# Power.net
KiCad netlist of a schematic drawn in Altium Designer
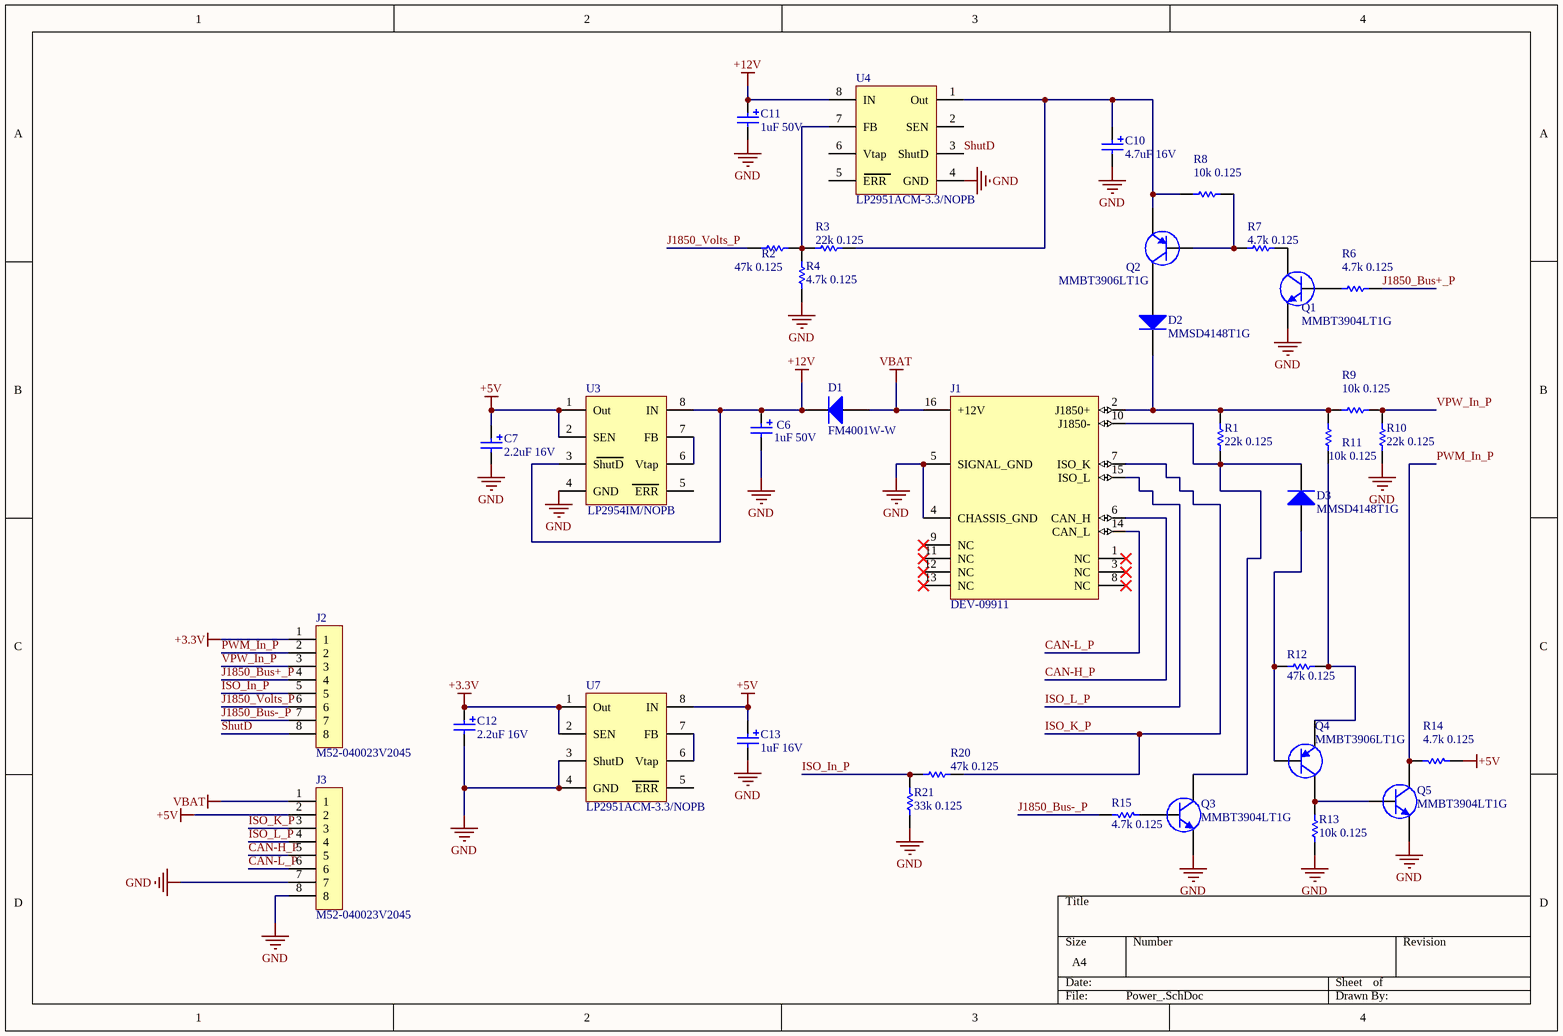
[diagram p0: Power_.SchDoc]

(export (version "E")
  (design (tool "Eeschema 10.0.6"))
  (components
    (comp (ref "C6")
      (value "1uF 50V")
      (footprint "C1005")
      (description "Surface-Mount Electrolitic Tantalum Capacitor, 1uF, 20% Tolerance, 1005 Size, 50V")
      (fields (field (name "PUBLISHER") "Altium Limited"))
      (libsource (lib "OBDII-components") (part "298D105X0050P2T"))
    )
    (comp (ref "C7")
      (value "2.2uF 16V")
      (footprint "C0603")
      (description "Surface-Mount Electrolitic Tantalum Capacitor, 2.2uF, 10% Tolerance, 0603 Size, 16V")
      (fields (field (name "PUBLISHER") "Altium Limited"))
      (libsource (lib "OBDII-components") (part "298D225X0016M2T"))
    )
    (comp (ref "C10")
      (value "4.7uF 16V")
      (footprint "C1005")
      (description "Surface-Mount Electrolitic Tantalum Capacitor, 4.7uF, 20% Tolerance, 1005 Size, 16V")
      (fields (field (name "PUBLISHER") "Altium Limited"))
      (libsource (lib "OBDII-components") (part "298D475X0016P2T"))
    )
    (comp (ref "C11")
      (value "1uF 50V")
      (footprint "C1005")
      (description "Surface-Mount Electrolitic Tantalum Capacitor, 1uF, 20% Tolerance, 1005 Size, 50V")
      (fields (field (name "PUBLISHER") "Altium Limited"))
      (libsource (lib "OBDII-components") (part "298D105X0050P2T"))
    )
    (comp (ref "C12")
      (value "2.2uF 16V")
      (footprint "C0603")
      (description "Surface-Mount Electrolitic Tantalum Capacitor, 2.2uF, 10% Tolerance, 0603 Size, 16V")
      (fields (field (name "PUBLISHER") "Altium Limited"))
      (libsource (lib "OBDII-components") (part "298D225X0016M2T"))
    )
    (comp (ref "C13")
      (value "1uF 16V")
      (footprint "C0603")
      (description "Surface-Mount Electrolitic Tantalum Capacitor, 1uF, 10% Tolerance, 0603 Size, 16V")
      (fields (field (name "PUBLISHER") "Altium Limited"))
      (libsource (lib "OBDII-components") (part "298D105X9016M2T"))
    )
    (comp (ref "D1")
      (value "FM4001W-W")
      (footprint "SMA,2.8mm")
      (description "1 Amp 50V  Rectifier")
      (libsource (lib "OBDII-components") (part "FM4001W-W"))
    )
    (comp (ref "D2")
      (value "MMSD4148T1G")
      (footprint "SOD123")
      (description "High Conductance Fast Diode")
      (fields
        (field (name "MANUFACTURER") "OnSemi")
        (field (name "PUBLISHER") "Vanteon")
        (field (name "APPROVED") "M. Jablonski")
      )
      (libsource (lib "OBDII-components") (part "MMSD4148T1G"))
    )
    (comp (ref "D3")
      (value "MMSD4148T1G")
      (footprint "SOD123")
      (description "High Conductance Fast Diode")
      (fields
        (field (name "MANUFACTURER") "OnSemi")
        (field (name "PUBLISHER") "Vanteon")
        (field (name "APPROVED") "M. Jablonski")
      )
      (libsource (lib "OBDII-components") (part "MMSD4148T1G"))
    )
    (comp (ref "J1")
      (value "DEV-09911")
      (footprint "DEV-09911 - II")
      (description "OBD-II Connector")
      (fields (field (name "MANUFACTURER") "SparkFun Electronics"))
      (libsource (lib "OBDII-components") (part "OBDII_DEV-09911"))
    )
    (comp (ref "J2")
      (value "M52-040023V2045")
      (footprint "M52-040023V2045")
      (description "CONN HEADER .050\" 20POS PCB GOLD")
      (fields (field (name "MANUFACTURER") "Harwin"))
      (libsource (lib "OBDII-components") (part "M52-040023V2045"))
    )
    (comp (ref "J3")
      (value "M52-040023V2045")
      (footprint "M52-040023V2045")
      (description "CONN HEADER .050\" 20POS PCB GOLD")
      (fields (field (name "MANUFACTURER") "Harwin"))
      (libsource (lib "OBDII-components") (part "M52-040023V2045"))
    )
    (comp (ref "Q1")
      (value "MMBT3904LT1G")
      (footprint "SOT23")
      (description "NPN 3904 General Purpose Amplifier")
      (fields
        (field (name "MANUFACTURER") "ON Semiconductor")
        (field (name "PUBLISHER") "Vanteon")
        (field (name "APPROVED") "Yes by Implemenation")
      )
      (libsource (lib "OBDII-components") (part "MMBT3904LT1G"))
    )
    (comp (ref "Q2")
      (value "MMBT3906LT1G")
      (footprint "SOT23")
      (description "PNP 3906 General Purpose Amplifier")
      (fields
        (field (name "MANUFACTURER") "ON Semiconductor")
        (field (name "PUBLISHER") "Vanteon")
        (field (name "APPROVED") "Yes by Implemenation")
      )
      (libsource (lib "OBDII-components") (part "MMBT3906LT1G"))
    )
    (comp (ref "Q3")
      (value "MMBT3904LT1G")
      (footprint "SOT23")
      (description "NPN 3904 General Purpose Amplifier")
      (fields
        (field (name "MANUFACTURER") "ON Semiconductor")
        (field (name "PUBLISHER") "Vanteon")
        (field (name "APPROVED") "Yes by Implemenation")
      )
      (libsource (lib "OBDII-components") (part "MMBT3904LT1G"))
    )
    (comp (ref "Q4")
      (value "MMBT3906LT1G")
      (footprint "SOT23")
      (description "PNP 3906 General Purpose Amplifier")
      (fields
        (field (name "MANUFACTURER") "ON Semiconductor")
        (field (name "PUBLISHER") "Vanteon")
        (field (name "APPROVED") "Yes by Implemenation")
      )
      (libsource (lib "OBDII-components") (part "MMBT3906LT1G"))
    )
    (comp (ref "Q5")
      (value "MMBT3904LT1G")
      (footprint "SOT23")
      (description "NPN 3904 General Purpose Amplifier")
      (fields
        (field (name "MANUFACTURER") "ON Semiconductor")
        (field (name "PUBLISHER") "Vanteon")
        (field (name "APPROVED") "Yes by Implemenation")
      )
      (libsource (lib "OBDII-components") (part "MMBT3904LT1G"))
    )
    (comp (ref "R1")
      (value "22k 0.125")
      (footprint "ERA-0805")
      (description "Rectangular Thick Film Chip Resistor, 22 kOhm, 0.1% Tolerance, 0805 Size, 0.125 W")
      (libsource (lib "OBDII-components") (part "ERA-6AEB223V"))
    )
    (comp (ref "R2")
      (value "47k 0.125")
      (footprint "ERA-0805")
      (description "Rectangular Thick Film Chip Resistor, 47 kOhm, 0.1% Tolerance, 0805 Size, 0.125 W")
      (libsource (lib "OBDII-components") (part "ERA-6AEB473V"))
    )
    (comp (ref "R3")
      (value "22k 0.125")
      (footprint "ERA-0805")
      (description "Rectangular Thick Film Chip Resistor, 22 kOhm, 0.1% Tolerance, 0805 Size, 0.125 W")
      (libsource (lib "OBDII-components") (part "ERA-6AEB223V"))
    )
    (comp (ref "R4")
      (value "4.7k 0.125")
      (footprint "ERA-0805")
      (description "Rectangular Thick Film Chip Resistor, 4.7 kOhm, 0.1% Tolerance, 0805 Size, 0.125 W")
      (libsource (lib "OBDII-components") (part "ERA-6AEB472V"))
    )
    (comp (ref "R6")
      (value "4.7k 0.125")
      (footprint "ERA-0805")
      (description "Rectangular Thick Film Chip Resistor, 4.7 kOhm, 0.1% Tolerance, 0805 Size, 0.125 W")
      (libsource (lib "OBDII-components") (part "ERA-6AEB472V"))
    )
    (comp (ref "R7")
      (value "4.7k 0.125")
      (footprint "ERA-0805")
      (description "Rectangular Thick Film Chip Resistor, 4.7 kOhm, 0.1% Tolerance, 0805 Size, 0.125 W")
      (libsource (lib "OBDII-components") (part "ERA-6AEB472V"))
    )
    (comp (ref "R8")
      (value "10k 0.125")
      (footprint "ERA-0805")
      (description "Rectangular Thick Film Chip Resistor, 10 kOhm, 0.1% Tolerance, 0805 Size, 0.125 W")
      (libsource (lib "OBDII-components") (part "ERA-6AEB103V"))
    )
    (comp (ref "R9")
      (value "10k 0.125")
      (footprint "ERA-0805")
      (description "Rectangular Thick Film Chip Resistor, 10 kOhm, 0.1% Tolerance, 0805 Size, 0.125 W")
      (libsource (lib "OBDII-components") (part "ERA-6AEB103V"))
    )
    (comp (ref "R10")
      (value "22k 0.125")
      (footprint "ERA-0805")
      (description "Rectangular Thick Film Chip Resistor, 22 kOhm, 0.1% Tolerance, 0805 Size, 0.125 W")
      (libsource (lib "OBDII-components") (part "ERA-6AEB223V"))
    )
    (comp (ref "R11")
      (value "10k 0.125")
      (footprint "ERA-0805")
      (description "Rectangular Thick Film Chip Resistor, 10 kOhm, 0.1% Tolerance, 0805 Size, 0.125 W")
      (libsource (lib "OBDII-components") (part "ERA-6AEB103V"))
    )
    (comp (ref "R12")
      (value "47k 0.125")
      (footprint "ERA-0805")
      (description "Rectangular Thick Film Chip Resistor, 47 kOhm, 0.1% Tolerance, 0805 Size, 0.125 W")
      (libsource (lib "OBDII-components") (part "ERA-6AEB473V"))
    )
    (comp (ref "R13")
      (value "10k 0.125")
      (footprint "ERA-0805")
      (description "Rectangular Thick Film Chip Resistor, 10 kOhm, 0.1% Tolerance, 0805 Size, 0.125 W")
      (libsource (lib "OBDII-components") (part "ERA-6AEB103V"))
    )
    (comp (ref "R14")
      (value "4.7k 0.125")
      (footprint "ERA-0805")
      (description "Rectangular Thick Film Chip Resistor, 4.7 kOhm, 0.1% Tolerance, 0805 Size, 0.125 W")
      (libsource (lib "OBDII-components") (part "ERA-6AEB472V"))
    )
    (comp (ref "R15")
      (value "4.7k 0.125")
      (footprint "ERA-0805")
      (description "Rectangular Thick Film Chip Resistor, 4.7 kOhm, 0.1% Tolerance, 0805 Size, 0.125 W")
      (libsource (lib "OBDII-components") (part "ERA-6AEB472V"))
    )
    (comp (ref "R20")
      (value "47k 0.125")
      (footprint "ERA-0805")
      (description "Rectangular Thick Film Chip Resistor, 47 kOhm, 0.1% Tolerance, 0805 Size, 0.125 W")
      (libsource (lib "OBDII-components") (part "ERA-6AEB473V"))
    )
    (comp (ref "R21")
      (value "33k 0.125")
      (footprint "ERA-0805")
      (description "Rectangular Thick Film Chip Resistor, 33 kOhm, 0.1% Tolerance, 0805 Size, 0.125 W")
      (libsource (lib "OBDII-components") (part "ERA-6AEB333V"))
    )
    (comp (ref "U3")
      (value "LP2954IM/NOPB")
      (footprint "SOIC8N")
      (description "LDO Voltage Regulators  1.2V-29V 0.25A SOIC8")
      (fields
        (field (name "MANUFACTURER") "Texas Instruments")
        (field (name "APPROVED") "Yes by Implementation")
      )
      (libsource (lib "OBDII-components") (part "LP2954IM/NOPB"))
    )
    (comp (ref "U4")
      (value "LP2951ACM-3.3/NOPB")
      (footprint "SOIC8N")
      (description "LDO Voltage Regulators  1.2V-37V 0.1A SOIC8")
      (fields
        (field (name "MANUFACTURER") "Texas Instruments")
        (field (name "APPROVED") "Yes by Implementation")
      )
      (libsource (lib "") (part "LP2951ACM-3.3/NOPB_1"))
    )
    (comp (ref "U7")
      (value "LP2951ACM-3.3/NOPB")
      (footprint "SOIC8N")
      (description "LDO Voltage Regulators  1.2V-37V 0.1A SOIC8")
      (fields
        (field (name "MANUFACTURER") "Texas Instruments")
        (field (name "APPROVED") "Yes by Implementation")
      )
      (libsource (lib "OBDII-components") (part "LP2951ACM-3.3/NOPB"))
    )
  )
  (nets
    (net (code "1") (name "+3.3V") (class "Default")
      (node (ref "C12") (pin "1") (pinfunction "1_1") (pintype "passive"))
      (node (ref "J2") (pin "1") (pinfunction "1_1") (pintype "passive"))
      (node (ref "U7") (pin "1") (pinfunction "Out_1") (pintype "power_in"))
      (node (ref "U7") (pin "2") (pinfunction "SEN_2") (pintype "passive"))
    )
    (net (code "2") (name "+5V") (class "Default")
      (node (ref "C13") (pin "1") (pinfunction "1_1") (pintype "passive"))
      (node (ref "C7") (pin "1") (pinfunction "1_1") (pintype "passive"))
      (node (ref "J3") (pin "2") (pinfunction "2_2") (pintype "passive"))
      (node (ref "R14") (pin "1") (pinfunction "1_1") (pintype "passive"))
      (node (ref "U3") (pin "1") (pinfunction "Out_1") (pintype "power_in"))
      (node (ref "U3") (pin "2") (pinfunction "SEN_2") (pintype "passive"))
      (node (ref "U7") (pin "8") (pinfunction "IN_8") (pintype "passive"))
    )
    (net (code "3") (name "+12V") (class "Default")
      (node (ref "C11") (pin "1") (pinfunction "1_1") (pintype "passive"))
      (node (ref "C6") (pin "1") (pinfunction "1_1") (pintype "passive"))
      (node (ref "D1") (pin "2") (pinfunction "K_2") (pintype "passive"))
      (node (ref "U3") (pin "3") (pinfunction "ShutD_3") (pintype "passive"))
      (node (ref "U3") (pin "8") (pinfunction "IN_8") (pintype "passive"))
      (node (ref "U4") (pin "8") (pinfunction "IN_8") (pintype "passive"))
    )
    (net (code "4") (name "/CAN-H_P") (class "Default")
      (node (ref "J1") (pin "6") (pinfunction "CAN_H_6") (pintype "bidirectional"))
      (node (ref "J3") (pin "5") (pinfunction "5_5") (pintype "passive"))
    )
    (net (code "5") (name "/CAN-L_P") (class "Default")
      (node (ref "J1") (pin "14") (pinfunction "CAN_L_14") (pintype "bidirectional"))
      (node (ref "J3") (pin "6") (pinfunction "6_6") (pintype "passive"))
    )
    (net (code "6") (name "/ISO_In_P") (class "Default")
      (node (ref "J2") (pin "5") (pinfunction "5_5") (pintype "passive"))
      (node (ref "R20") (pin "1") (pinfunction "1_1") (pintype "passive"))
      (node (ref "R21") (pin "2") (pinfunction "2_2") (pintype "passive"))
    )
    (net (code "7") (name "/ISO_K_P") (class "Default")
      (node (ref "J1") (pin "7") (pinfunction "ISO_K_7") (pintype "bidirectional"))
      (node (ref "J3") (pin "3") (pinfunction "3_3") (pintype "passive"))
      (node (ref "R20") (pin "2") (pinfunction "2_2") (pintype "passive"))
    )
    (net (code "8") (name "/ISO_L_P") (class "Default")
      (node (ref "J1") (pin "15") (pinfunction "ISO_L_15") (pintype "bidirectional"))
      (node (ref "J3") (pin "4") (pinfunction "4_4") (pintype "passive"))
    )
    (net (code "9") (name "/J1850_Bus+_P") (class "Default")
      (node (ref "J2") (pin "4") (pinfunction "4_4") (pintype "passive"))
      (node (ref "R6") (pin "2") (pinfunction "2_2") (pintype "passive"))
    )
    (net (code "10") (name "/J1850_Bus-_P") (class "Default")
      (node (ref "J2") (pin "7") (pinfunction "7_7") (pintype "passive"))
      (node (ref "R15") (pin "2") (pinfunction "2_2") (pintype "passive"))
    )
    (net (code "11") (name "/J1850_Volts_P") (class "Default")
      (node (ref "J2") (pin "6") (pinfunction "6_6") (pintype "passive"))
      (node (ref "R2") (pin "1") (pinfunction "1_1") (pintype "passive"))
    )
    (net (code "12") (name "/PWM_In_P") (class "Default")
      (node (ref "J2") (pin "2") (pinfunction "2_2") (pintype "passive"))
      (node (ref "Q5") (pin "3") (pinfunction "C_3") (pintype "passive"))
      (node (ref "R14") (pin "2") (pinfunction "2_2") (pintype "passive"))
    )
    (net (code "13") (name "/ShutD") (class "Default")
      (node (ref "J2") (pin "8") (pinfunction "8_8") (pintype "passive"))
      (node (ref "U4") (pin "3") (pinfunction "ShutD_3") (pintype "passive"))
    )
    (net (code "14") (name "/VPW_In_P") (class "Default")
      (node (ref "J2") (pin "3") (pinfunction "3_3") (pintype "passive"))
      (node (ref "R10") (pin "2") (pinfunction "2_2") (pintype "passive"))
      (node (ref "R9") (pin "1") (pinfunction "1_1") (pintype "passive"))
    )
    (net (code "15") (name "GND") (class "Default")
      (node (ref "C10") (pin "2") (pinfunction "2_2") (pintype "passive"))
      (node (ref "C11") (pin "2") (pinfunction "2_2") (pintype "passive"))
      (node (ref "C12") (pin "2") (pinfunction "2_2") (pintype "passive"))
      (node (ref "C13") (pin "2") (pinfunction "2_2") (pintype "passive"))
      (node (ref "C6") (pin "2") (pinfunction "2_2") (pintype "passive"))
      (node (ref "C7") (pin "2") (pinfunction "2_2") (pintype "passive"))
      (node (ref "J1") (pin "4") (pinfunction "CHASSIS_GND_4") (pintype "power_in"))
      (node (ref "J1") (pin "5") (pinfunction "SIGNAL_GND_5") (pintype "power_in"))
      (node (ref "J3") (pin "7") (pinfunction "7_7") (pintype "passive"))
      (node (ref "J3") (pin "8") (pinfunction "8_8") (pintype "passive"))
      (node (ref "Q1") (pin "2") (pinfunction "E_2") (pintype "passive"))
      (node (ref "Q3") (pin "2") (pinfunction "E_2") (pintype "passive"))
      (node (ref "Q5") (pin "2") (pinfunction "E_2") (pintype "passive"))
      (node (ref "R10") (pin "1") (pinfunction "1_1") (pintype "passive"))
      (node (ref "R13") (pin "2") (pinfunction "2_2") (pintype "passive"))
      (node (ref "R21") (pin "1") (pinfunction "1_1") (pintype "passive"))
      (node (ref "R4") (pin "1") (pinfunction "1_1") (pintype "passive"))
      (node (ref "U3") (pin "4") (pinfunction "GND_4") (pintype "power_in"))
      (node (ref "U4") (pin "4") (pinfunction "GND_4") (pintype "power_in"))
      (node (ref "U7") (pin "3") (pinfunction "ShutD_3") (pintype "passive"))
      (node (ref "U7") (pin "4") (pinfunction "GND_4") (pintype "power_in"))
    )
    (net (code "16") (name "Net-(D2-A)") (class "Default")
      (node (ref "D2") (pin "1") (pinfunction "A_1") (pintype "passive"))
      (node (ref "Q2") (pin "3") (pinfunction "C_3") (pintype "passive"))
    )
    (net (code "17") (name "Net-(D2-C)") (class "Default")
      (node (ref "D2") (pin "2") (pinfunction "C_2") (pintype "passive"))
      (node (ref "J1") (pin "2") (pinfunction "J1850+_2") (pintype "bidirectional"))
      (node (ref "R1") (pin "2") (pinfunction "2_2") (pintype "passive"))
      (node (ref "R11") (pin "1") (pinfunction "1_1") (pintype "passive"))
      (node (ref "R9") (pin "2") (pinfunction "2_2") (pintype "passive"))
    )
    (net (code "18") (name "Net-(D3-A)") (class "Default")
      (node (ref "D3") (pin "1") (pinfunction "A_1") (pintype "passive"))
      (node (ref "Q4") (pin "1") (pinfunction "B_1") (pintype "passive"))
      (node (ref "R12") (pin "1") (pinfunction "1_1") (pintype "passive"))
    )
    (net (code "19") (name "Net-(D3-C)") (class "Default")
      (node (ref "D3") (pin "2") (pinfunction "C_2") (pintype "passive"))
      (node (ref "J1") (pin "10") (pinfunction "J1850-_10") (pintype "bidirectional"))
      (node (ref "Q3") (pin "3") (pinfunction "C_3") (pintype "passive"))
      (node (ref "R1") (pin "1") (pinfunction "1_1") (pintype "passive"))
    )
    (net (code "20") (name "Net-(Q1-B)") (class "Default")
      (node (ref "Q1") (pin "1") (pinfunction "B_1") (pintype "passive"))
      (node (ref "R6") (pin "1") (pinfunction "1_1") (pintype "passive"))
    )
    (net (code "21") (name "Net-(Q1-C)") (class "Default")
      (node (ref "Q1") (pin "3") (pinfunction "C_3") (pintype "passive"))
      (node (ref "R7") (pin "2") (pinfunction "2_2") (pintype "passive"))
    )
    (net (code "22") (name "Net-(Q2-B)") (class "Default")
      (node (ref "Q2") (pin "1") (pinfunction "B_1") (pintype "passive"))
      (node (ref "R7") (pin "1") (pinfunction "1_1") (pintype "passive"))
      (node (ref "R8") (pin "1") (pinfunction "1_1") (pintype "passive"))
    )
    (net (code "23") (name "Net-(Q2-E)") (class "Default")
      (node (ref "C10") (pin "1") (pinfunction "1_1") (pintype "passive"))
      (node (ref "Q2") (pin "2") (pinfunction "E_2") (pintype "passive"))
      (node (ref "R3") (pin "2") (pinfunction "2_2") (pintype "passive"))
      (node (ref "R8") (pin "2") (pinfunction "2_2") (pintype "passive"))
      (node (ref "U4") (pin "1") (pinfunction "Out_1") (pintype "power_in"))
    )
    (net (code "24") (name "Net-(Q3-B)") (class "Default")
      (node (ref "Q3") (pin "1") (pinfunction "B_1") (pintype "passive"))
      (node (ref "R15") (pin "1") (pinfunction "1_1") (pintype "passive"))
    )
    (net (code "25") (name "Net-(Q4-C)") (class "Default")
      (node (ref "Q4") (pin "3") (pinfunction "C_3") (pintype "passive"))
      (node (ref "Q5") (pin "1") (pinfunction "B_1") (pintype "passive"))
      (node (ref "R13") (pin "1") (pinfunction "1_1") (pintype "passive"))
    )
    (net (code "26") (name "Net-(Q4-E)") (class "Default")
      (node (ref "Q4") (pin "2") (pinfunction "E_2") (pintype "passive"))
      (node (ref "R11") (pin "2") (pinfunction "2_2") (pintype "passive"))
      (node (ref "R12") (pin "2") (pinfunction "2_2") (pintype "passive"))
    )
    (net (code "27") (name "Net-(U3-FB)") (class "Default")
      (node (ref "U3") (pin "6") (pinfunction "Vtap_6") (pintype "passive"))
      (node (ref "U3") (pin "7") (pinfunction "FB_7") (pintype "passive"))
    )
    (net (code "28") (name "Net-(U4-FB)") (class "Default")
      (node (ref "R2") (pin "2") (pinfunction "2_2") (pintype "passive"))
      (node (ref "R3") (pin "1") (pinfunction "1_1") (pintype "passive"))
      (node (ref "R4") (pin "2") (pinfunction "2_2") (pintype "passive"))
      (node (ref "U4") (pin "7") (pinfunction "FB_7") (pintype "passive"))
    )
    (net (code "29") (name "Net-(U7-FB)") (class "Default")
      (node (ref "U7") (pin "6") (pinfunction "Vtap_6") (pintype "passive"))
      (node (ref "U7") (pin "7") (pinfunction "FB_7") (pintype "passive"))
    )
    (net (code "30") (name "VBAT") (class "Default")
      (node (ref "D1") (pin "1") (pinfunction "A_1") (pintype "passive"))
      (node (ref "J1") (pin "16") (pinfunction "+12V_16") (pintype "power_in"))
      (node (ref "J3") (pin "1") (pinfunction "1_1") (pintype "passive"))
    )
    (net (code "31") (name "unconnected-(J1-NC-Pad1)") (class "Default")
      (node (ref "J1") (pin "1") (pinfunction "NC_1") (pintype "passive+no_connect"))
    )
    (net (code "32") (name "unconnected-(J1-NC-Pad3)") (class "Default")
      (node (ref "J1") (pin "3") (pinfunction "NC_3") (pintype "passive+no_connect"))
    )
    (net (code "33") (name "unconnected-(J1-NC-Pad8)") (class "Default")
      (node (ref "J1") (pin "8") (pinfunction "NC_8") (pintype "passive+no_connect"))
    )
    (net (code "34") (name "unconnected-(J1-NC-Pad9)") (class "Default")
      (node (ref "J1") (pin "9") (pinfunction "NC_9") (pintype "passive+no_connect"))
    )
    (net (code "35") (name "unconnected-(J1-NC-Pad11)") (class "Default")
      (node (ref "J1") (pin "11") (pinfunction "NC_11") (pintype "passive+no_connect"))
    )
    (net (code "36") (name "unconnected-(J1-NC-Pad12)") (class "Default")
      (node (ref "J1") (pin "12") (pinfunction "NC_12") (pintype "passive+no_connect"))
    )
    (net (code "37") (name "unconnected-(J1-NC-Pad13)") (class "Default")
      (node (ref "J1") (pin "13") (pinfunction "NC_13") (pintype "passive+no_connect"))
    )
    (net (code "38") (name "unconnected-(U3-ERR-Pad5)") (class "Default")
      (node (ref "U3") (pin "5") (pinfunction "ERR_5") (pintype "passive"))
    )
    (net (code "39") (name "unconnected-(U4-ERR-Pad5)") (class "Default")
      (node (ref "U4") (pin "5") (pinfunction "ERR_5") (pintype "passive"))
    )
    (net (code "40") (name "unconnected-(U4-SEN-Pad2)") (class "Default")
      (node (ref "U4") (pin "2") (pinfunction "SEN_2") (pintype "passive"))
    )
    (net (code "41") (name "unconnected-(U4-Vtap-Pad6)") (class "Default")
      (node (ref "U4") (pin "6") (pinfunction "Vtap_6") (pintype "passive"))
    )
    (net (code "42") (name "unconnected-(U7-ERR-Pad5)") (class "Default")
      (node (ref "U7") (pin "5") (pinfunction "ERR_5") (pintype "passive"))
    )
  )
)
